# main.net
KiCad netlist of a schematic drawn in Altium Designer
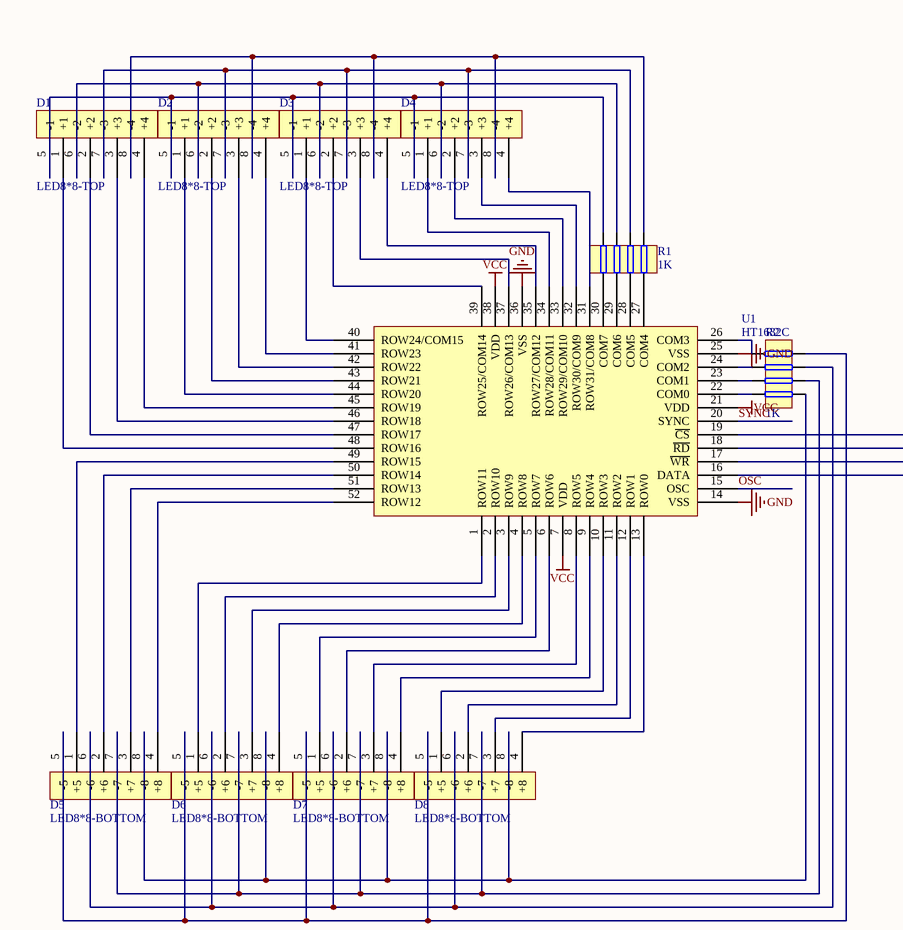
[diagram p0: main.SchDoc, top left]
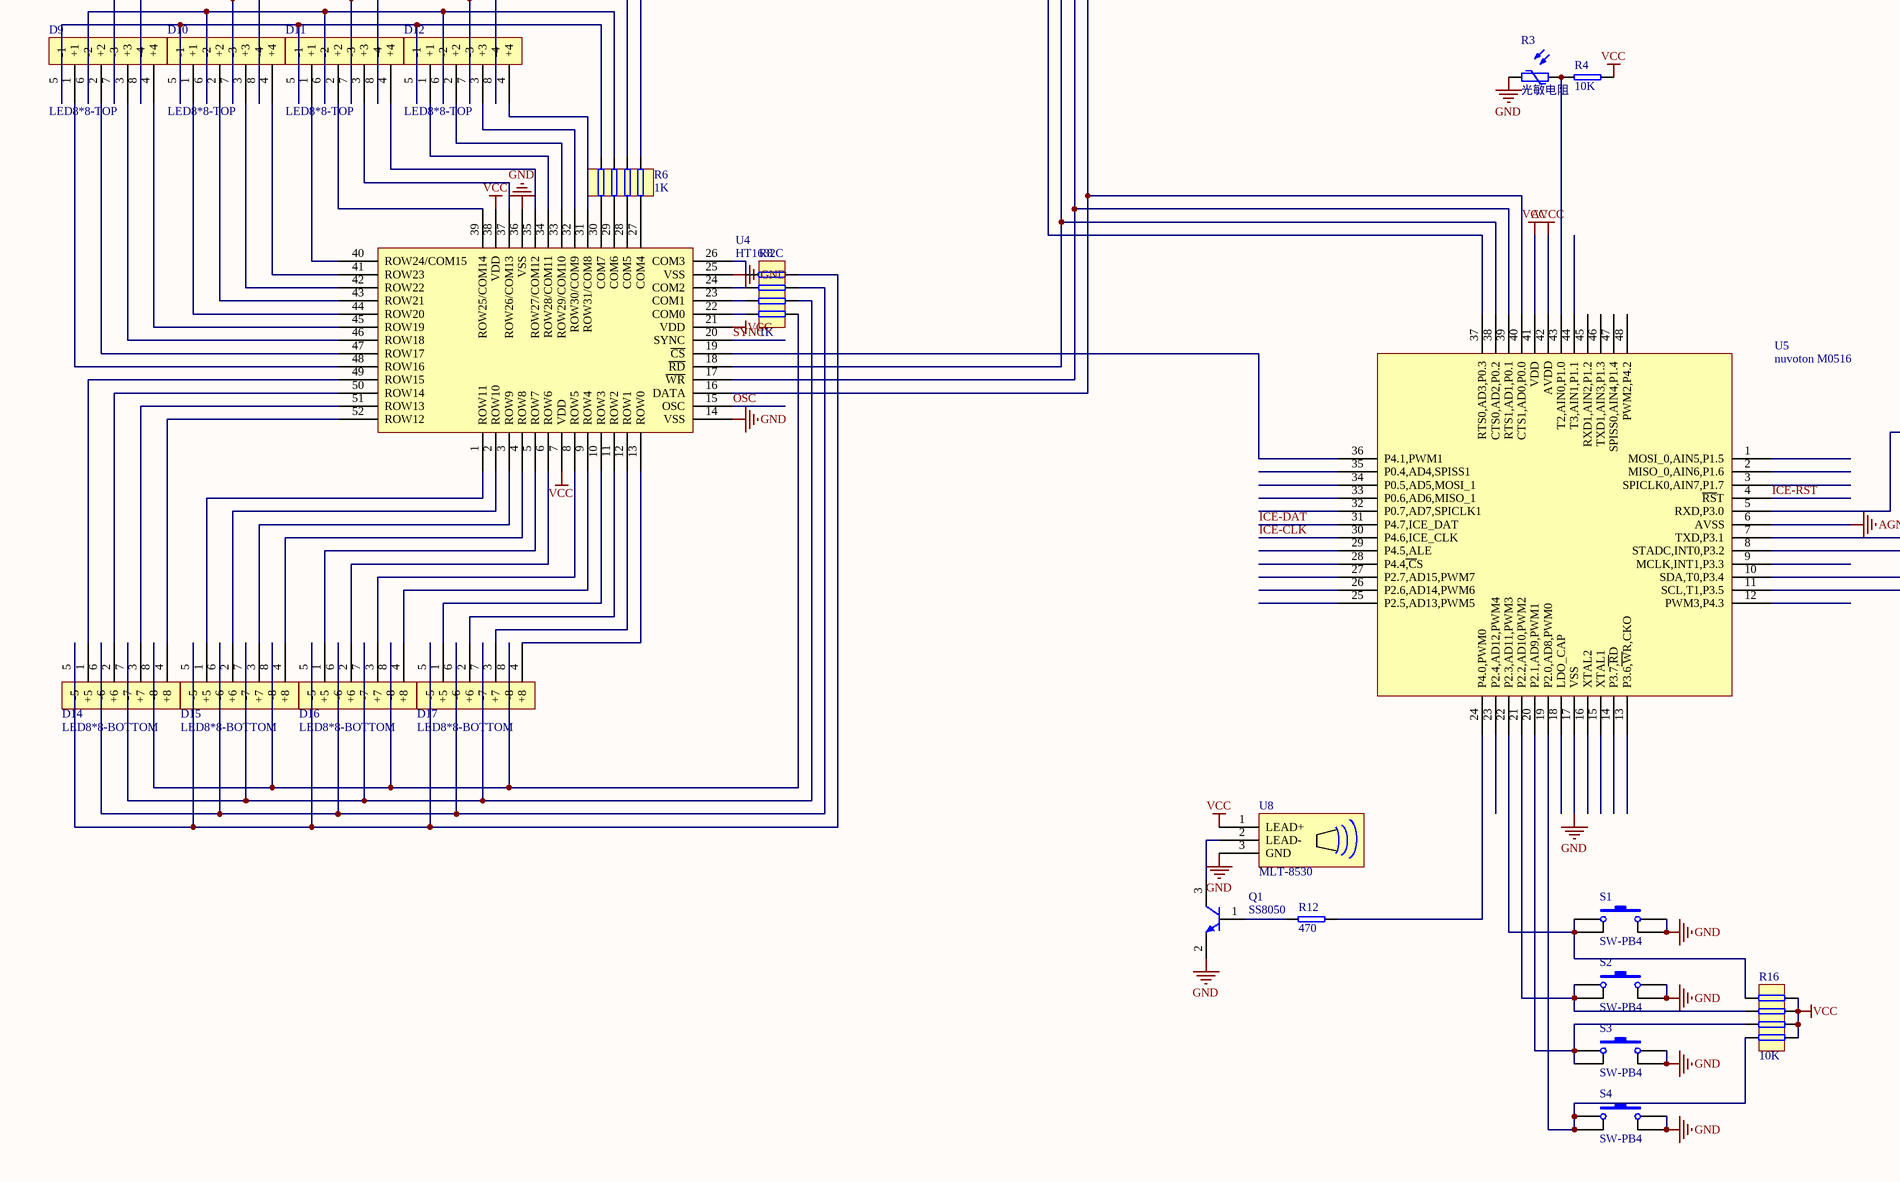
[diagram p1: main.SchDoc, bottom left]
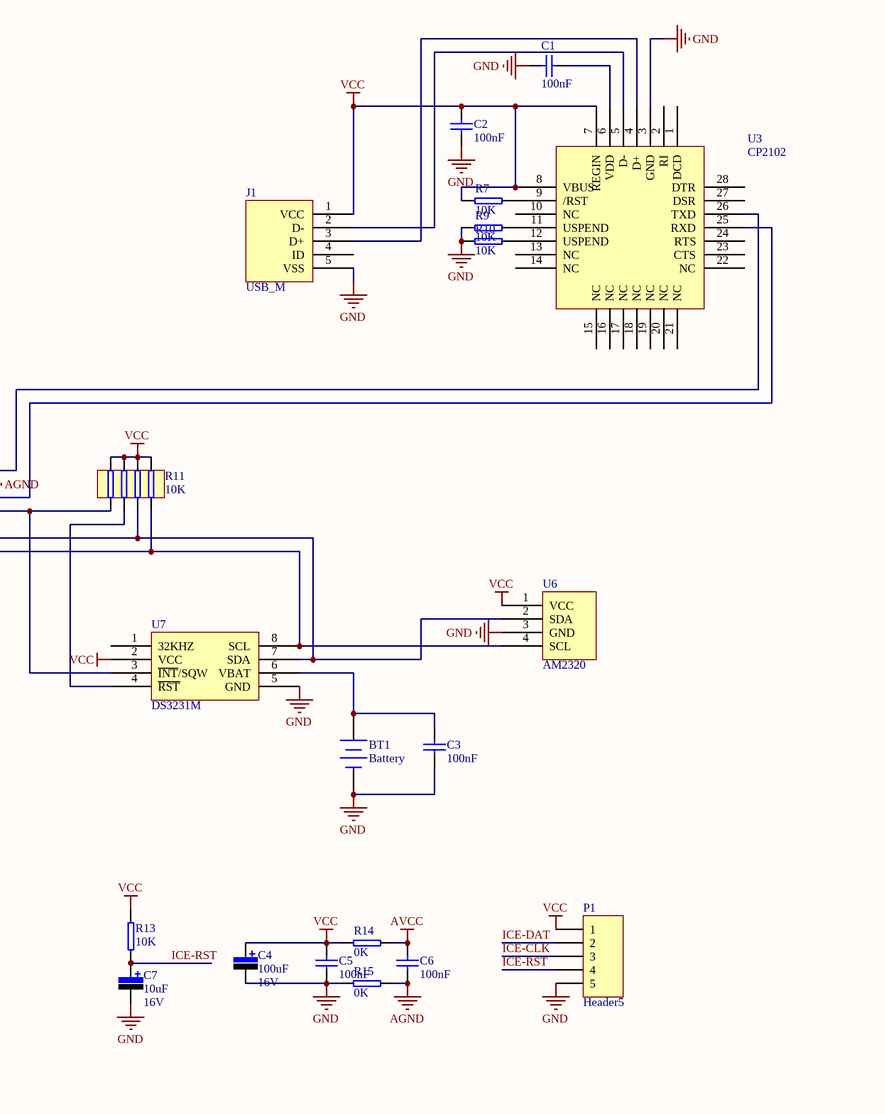
[diagram p2: main.SchDoc, bottom right]

(export (version "E")
  (design (tool "Eeschema 10.0.6"))
  (components
    (comp (ref "BT1")
      (value "Battery")
      (footprint "CR2032-2-1")
      (description "备份电池")
      (fields (field (name "PUBLISHER") "Altium Limited"))
      (libsource (lib "leonLib") (part "Battery"))
    )
    (comp (ref "C1")
      (value "100nF")
      (footprint "C-RAD-0603")
      (description "无极性电容")
      (fields (field (name "Comment") "Cap") (field (name "PUBLISHER") "Altium Limited"))
      (libsource (lib "leonLib") (part "Cap"))
    )
    (comp (ref "C2")
      (value "100nF")
      (footprint "C-RAD-0603")
      (description "无极性电容")
      (fields (field (name "Comment") "Cap") (field (name "PUBLISHER") "Altium Limited"))
      (libsource (lib "leonLib") (part "Cap"))
    )
    (comp (ref "C3")
      (value "100nF")
      (footprint "C-RAD-0603")
      (description "无极性电容")
      (fields (field (name "Comment") "Cap") (field (name "PUBLISHER") "Altium Limited"))
      (libsource (lib "leonLib") (part "Cap"))
    )
    (comp (ref "C4")
      (value "100uF")
      (footprint "CAP-3216")
      (description "极性电解电容")
      (fields
        (field (name "VOL") "16V")
        (field (name "Comment") "Cap Pol")
        (field (name "PUBLISHER") "Altium Limited")
      )
      (libsource (lib "leonLib") (part "Cap Pol"))
    )
    (comp (ref "C5")
      (value "100nF")
      (footprint "C-RAD-0603")
      (description "无极性电容")
      (fields (field (name "Comment") "Cap") (field (name "PUBLISHER") "Altium Limited"))
      (libsource (lib "leonLib") (part "Cap"))
    )
    (comp (ref "C6")
      (value "100nF")
      (footprint "C-RAD-0603")
      (description "无极性电容")
      (fields (field (name "Comment") "Cap") (field (name "PUBLISHER") "Altium Limited"))
      (libsource (lib "leonLib") (part "Cap"))
    )
    (comp (ref "C7")
      (value "10uF")
      (footprint "CAP-3216")
      (description "极性电解电容")
      (fields
        (field (name "VOL") "16V")
        (field (name "Comment") "Cap Pol")
        (field (name "PUBLISHER") "Altium Limited")
      )
      (libsource (lib "leonLib") (part "Cap Pol"))
    )
    (comp (ref "D1")
      (value "LED8*8-TOP")
      (footprint "LED8*8-half")
      (description "8*8LED点阵上半部分")
      (libsource (lib "leonLib") (part "LED8*8-TOP"))
    )
    (comp (ref "D2")
      (value "LED8*8-TOP")
      (footprint "LED8*8-half")
      (description "8*8LED点阵上半部分")
      (libsource (lib "leonLib") (part "LED8*8-TOP"))
    )
    (comp (ref "D3")
      (value "LED8*8-TOP")
      (footprint "LED8*8-half")
      (description "8*8LED点阵上半部分")
      (libsource (lib "leonLib") (part "LED8*8-TOP"))
    )
    (comp (ref "D4")
      (value "LED8*8-TOP")
      (footprint "LED8*8-half")
      (description "8*8LED点阵上半部分")
      (libsource (lib "leonLib") (part "LED8*8-TOP"))
    )
    (comp (ref "D5")
      (value "LED8*8-BOTTOM")
      (footprint "LED8*8-half")
      (description "8*8LED点阵下半部分")
      (libsource (lib "leonLib") (part "LED8*8-BOTTOM"))
    )
    (comp (ref "D6")
      (value "LED8*8-BOTTOM")
      (footprint "LED8*8-half")
      (description "8*8LED点阵下半部分")
      (libsource (lib "leonLib") (part "LED8*8-BOTTOM"))
    )
    (comp (ref "D7")
      (value "LED8*8-BOTTOM")
      (footprint "LED8*8-half")
      (description "8*8LED点阵下半部分")
      (libsource (lib "leonLib") (part "LED8*8-BOTTOM"))
    )
    (comp (ref "D8")
      (value "LED8*8-BOTTOM")
      (footprint "LED8*8-half")
      (description "8*8LED点阵下半部分")
      (libsource (lib "leonLib") (part "LED8*8-BOTTOM"))
    )
    (comp (ref "D9")
      (value "LED8*8-TOP")
      (footprint "LED8*8-half")
      (description "8*8LED点阵上半部分")
      (libsource (lib "leonLib") (part "LED8*8-TOP"))
    )
    (comp (ref "D10")
      (value "LED8*8-TOP")
      (footprint "LED8*8-half")
      (description "8*8LED点阵上半部分")
      (libsource (lib "leonLib") (part "LED8*8-TOP"))
    )
    (comp (ref "D11")
      (value "LED8*8-TOP")
      (footprint "LED8*8-half")
      (description "8*8LED点阵上半部分")
      (libsource (lib "leonLib") (part "LED8*8-TOP"))
    )
    (comp (ref "D12")
      (value "LED8*8-TOP")
      (footprint "LED8*8-half")
      (description "8*8LED点阵上半部分")
      (libsource (lib "leonLib") (part "LED8*8-TOP"))
    )
    (comp (ref "D14")
      (value "LED8*8-BOTTOM")
      (footprint "LED8*8-half")
      (description "8*8LED点阵下半部分")
      (libsource (lib "leonLib") (part "LED8*8-BOTTOM"))
    )
    (comp (ref "D15")
      (value "LED8*8-BOTTOM")
      (footprint "LED8*8-half")
      (description "8*8LED点阵下半部分")
      (libsource (lib "leonLib") (part "LED8*8-BOTTOM"))
    )
    (comp (ref "D16")
      (value "LED8*8-BOTTOM")
      (footprint "LED8*8-half")
      (description "8*8LED点阵下半部分")
      (libsource (lib "leonLib") (part "LED8*8-BOTTOM"))
    )
    (comp (ref "D17")
      (value "LED8*8-BOTTOM")
      (footprint "LED8*8-half")
      (description "8*8LED点阵下半部分")
      (libsource (lib "leonLib") (part "LED8*8-BOTTOM"))
    )
    (comp (ref "J1")
      (value "USB_M")
      (footprint "USB_MICRO")
      (description "MicroUSB接口")
      (libsource (lib "leonLib") (part "USB_M"))
    )
    (comp (ref "P1")
      (value "Header5")
      (footprint "HDR5X1_A")
      (description "接插件")
      (libsource (lib "leonLib") (part "Header5"))
    )
    (comp (ref "Q1")
      (value "SS8050")
      (footprint "SOT-23")
      (description "NPN贴片三极管")
      (fields (field (name "PUBLISHER") "Altium Limited"))
      (libsource (lib "leonLib") (part "SS8050"))
    )
    (comp (ref "R1")
      (value "1K")
      (footprint "RES0603ROW")
      (description "排阻0603*4")
      (libsource (lib "leonLib") (part "Res Row"))
    )
    (comp (ref "R2")
      (value "1K")
      (footprint "RES0603ROW")
      (description "排阻0603*4")
      (libsource (lib "") (part "Res Row_1"))
    )
    (comp (ref "R3") (value "光敏电阻") (footprint "RES3") (libsource (lib "leonLib") (part "res3")))
    (comp (ref "R4")
      (value "10K")
      (footprint "RES_0603")
      (description "贴片电阻")
      (fields (field (name "Comment") "Res1") (field (name "PUBLISHER") "Altium Limited"))
      (libsource (lib "") (part "Res1_1"))
    )
    (comp (ref "R6")
      (value "1K")
      (footprint "RES0603ROW")
      (description "排阻0603*4")
      (libsource (lib "leonLib") (part "Res Row"))
    )
    (comp (ref "R7")
      (value "10K")
      (footprint "RES_0603")
      (description "贴片电阻")
      (fields (field (name "Comment") "Res1") (field (name "PUBLISHER") "Altium Limited"))
      (libsource (lib "") (part "Res1_1"))
    )
    (comp (ref "R8")
      (value "1K")
      (footprint "RES0603ROW")
      (description "排阻0603*4")
      (libsource (lib "") (part "Res Row_1"))
    )
    (comp (ref "R9")
      (value "10K")
      (footprint "RES_0603")
      (description "贴片电阻")
      (fields (field (name "Comment") "Res1") (field (name "PUBLISHER") "Altium Limited"))
      (libsource (lib "") (part "Res1_1"))
    )
    (comp (ref "R10")
      (value "10K")
      (footprint "RES_0603")
      (description "贴片电阻")
      (fields (field (name "Comment") "Res1") (field (name "PUBLISHER") "Altium Limited"))
      (libsource (lib "") (part "Res1_1"))
    )
    (comp (ref "R11")
      (value "10K")
      (footprint "RES0603ROW")
      (description "排阻0603*4")
      (libsource (lib "leonLib") (part "Res Row"))
    )
    (comp (ref "R12")
      (value "470")
      (footprint "RES_0603")
      (description "贴片电阻")
      (fields (field (name "Comment") "Res1") (field (name "PUBLISHER") "Altium Limited"))
      (libsource (lib "") (part "Res1_1"))
    )
    (comp (ref "R13")
      (value "10K")
      (footprint "RES_0603")
      (description "贴片电阻")
      (fields (field (name "Comment") "Res1") (field (name "PUBLISHER") "Altium Limited"))
      (libsource (lib "leonLib") (part "Res1"))
    )
    (comp (ref "R14")
      (value "0K")
      (footprint "RES_0603")
      (description "贴片电阻")
      (fields (field (name "Comment") "Res1") (field (name "PUBLISHER") "Altium Limited"))
      (libsource (lib "") (part "Res1_1"))
    )
    (comp (ref "R15")
      (value "0K")
      (footprint "RES_0603")
      (description "贴片电阻")
      (fields (field (name "Comment") "Res1") (field (name "PUBLISHER") "Altium Limited"))
      (libsource (lib "") (part "Res1_1"))
    )
    (comp (ref "R16")
      (value "10K")
      (footprint "RES0603ROW")
      (description "排阻0603*4")
      (libsource (lib "") (part "Res Row_1"))
    )
    (comp (ref "S1")
      (value "SW-PB4")
      (footprint "SW_PB4_A2_4.5*4.5")
      (description "微动开关")
      (fields (field (name "PUBLISHER") "Altium Limited"))
      (libsource (lib "leonLib") (part "SW-PB4"))
    )
    (comp (ref "S2")
      (value "SW-PB4")
      (footprint "SW_PB4_A2_4.5*4.5")
      (description "微动开关")
      (fields (field (name "PUBLISHER") "Altium Limited"))
      (libsource (lib "leonLib") (part "SW-PB4"))
    )
    (comp (ref "S3")
      (value "SW-PB4")
      (footprint "SW_PB4_A2_4.5*4.5")
      (description "微动开关")
      (fields (field (name "PUBLISHER") "Altium Limited"))
      (libsource (lib "leonLib") (part "SW-PB4"))
    )
    (comp (ref "S4")
      (value "SW-PB4")
      (footprint "SW_PB4_A2_4.5*4.5")
      (description "微动开关")
      (fields (field (name "PUBLISHER") "Altium Limited"))
      (libsource (lib "leonLib") (part "SW-PB4"))
    )
    (comp (ref "U1")
      (value "HT1632C")
      (footprint "QFP52-14mm-1.0mm")
      (description "32×8 & 24×16 LED 驱动芯片")
      (libsource (lib "leonLib") (part "HT1632C"))
    )
    (comp (ref "U3")
      (value "CP2102")
      (footprint "QFN-28")
      (description "USB转TTL芯片")
      (libsource (lib "leonLib") (part "CP2102"))
    )
    (comp (ref "U4")
      (value "HT1632C")
      (footprint "QFP52-14mm-1.0mm")
      (description "32×8 & 24×16 LED 驱动芯片")
      (libsource (lib "leonLib") (part "HT1632C"))
    )
    (comp (ref "U5")
      (value "nuvoton M0516")
      (footprint "LQFP-48_7x7x05P")
      (description "新唐M0516单片机")
      (libsource (lib "leonLib") (part "nuvoton M0516"))
    )
    (comp (ref "U6")
      (value "AM2320")
      (footprint "HDR4X1_A")
      (description "温湿度传感器")
      (libsource (lib "leonLib") (part "AM2320"))
    )
    (comp (ref "U7")
      (value "DS3231M")
      (footprint "SOP-8")
      (description "实时时钟")
      (libsource (lib "leonLib") (part "DS3231M"))
    )
    (comp (ref "U8")
      (value "MLT-8530")
      (footprint "MLT-8530")
      (description "贴片蜂鸣器")
      (libsource (lib "leonLib") (part "MLT-8530"))
    )
  )
  (nets
    (net (code "1") (name "/ICE-CLK") (class "Default")
      (node (ref "P1") (pin "3") (pinfunction "3_3") (pintype "passive"))
      (node (ref "U5") (pin "30") (pinfunction "P4.6,ICE_CLK_30") (pintype "passive"))
    )
    (net (code "2") (name "/ICE-DAT") (class "Default")
      (node (ref "P1") (pin "2") (pinfunction "2_2") (pintype "passive"))
      (node (ref "U5") (pin "31") (pinfunction "P4.7,ICE_DAT_31") (pintype "passive"))
    )
    (net (code "3") (name "/ICE-RST") (class "Default")
      (node (ref "C7") (pin "1") (pinfunction "1_1") (pintype "passive"))
      (node (ref "P1") (pin "4") (pinfunction "4_4") (pintype "passive"))
      (node (ref "R13") (pin "1") (pinfunction "1_1") (pintype "passive"))
      (node (ref "U5") (pin "4") (pinfunction "~{RS}T_4") (pintype "passive"))
    )
    (net (code "4") (name "/OSC") (class "Default")
      (node (ref "U1") (pin "15") (pinfunction "OSC_15") (pintype "passive"))
      (node (ref "U4") (pin "15") (pinfunction "OSC_15") (pintype "passive"))
    )
    (net (code "5") (name "/SYNC") (class "Default")
      (node (ref "U1") (pin "20") (pinfunction "SYNC_20") (pintype "passive"))
      (node (ref "U4") (pin "20") (pinfunction "SYNC_20") (pintype "passive"))
    )
    (net (code "6") (name "AGND") (class "Default")
      (node (ref "C6") (pin "1") (pinfunction "1_1") (pintype "passive"))
      (node (ref "R15") (pin "2") (pinfunction "2_2") (pintype "passive"))
      (node (ref "U5") (pin "6") (pinfunction "AVSS_6") (pintype "passive"))
    )
    (net (code "7") (name "AVCC") (class "Default")
      (node (ref "C6") (pin "2") (pinfunction "2_2") (pintype "passive"))
      (node (ref "R14") (pin "2") (pinfunction "2_2") (pintype "passive"))
      (node (ref "U5") (pin "42") (pinfunction "AVDD_42") (pintype "passive"))
    )
    (net (code "8") (name "GND") (class "Default")
      (node (ref "BT1") (pin "2") (pinfunction "-_2") (pintype "passive"))
      (node (ref "C1") (pin "1") (pinfunction "1_1") (pintype "passive"))
      (node (ref "C2") (pin "1") (pinfunction "1_1") (pintype "passive"))
      (node (ref "C3") (pin "1") (pinfunction "1_1") (pintype "passive"))
      (node (ref "C4") (pin "2") (pinfunction "2_2") (pintype "passive"))
      (node (ref "C5") (pin "1") (pinfunction "1_1") (pintype "passive"))
      (node (ref "C7") (pin "2") (pinfunction "2_2") (pintype "passive"))
      (node (ref "J1") (pin "5") (pinfunction "VSS_5") (pintype "passive"))
      (node (ref "P1") (pin "5") (pinfunction "5_5") (pintype "passive"))
      (node (ref "Q1") (pin "2") (pinfunction "E_2") (pintype "passive"))
      (node (ref "R10") (pin "1") (pinfunction "1_1") (pintype "passive"))
      (node (ref "R15") (pin "1") (pinfunction "1_1") (pintype "passive"))
      (node (ref "R3") (pin "1") (pinfunction "1_1") (pintype "passive"))
      (node (ref "R9") (pin "1") (pinfunction "1_1") (pintype "passive"))
      (node (ref "S1") (pin "2") (pinfunction "2_2") (pintype "passive"))
      (node (ref "S1") (pin "3") (pinfunction "3_3") (pintype "passive"))
      (node (ref "S2") (pin "2") (pinfunction "2_2") (pintype "passive"))
      (node (ref "S2") (pin "3") (pinfunction "3_3") (pintype "passive"))
      (node (ref "S3") (pin "2") (pinfunction "2_2") (pintype "passive"))
      (node (ref "S3") (pin "3") (pinfunction "3_3") (pintype "passive"))
      (node (ref "S4") (pin "2") (pinfunction "2_2") (pintype "passive"))
      (node (ref "S4") (pin "3") (pinfunction "3_3") (pintype "passive"))
      (node (ref "U1") (pin "14") (pinfunction "VSS_14") (pintype "passive"))
      (node (ref "U1") (pin "25") (pinfunction "VSS_25") (pintype "passive"))
      (node (ref "U1") (pin "36") (pinfunction "VSS_36") (pintype "passive"))
      (node (ref "U3") (pin "3") (pinfunction "GND_3") (pintype "passive"))
      (node (ref "U4") (pin "14") (pinfunction "VSS_14") (pintype "passive"))
      (node (ref "U4") (pin "25") (pinfunction "VSS_25") (pintype "passive"))
      (node (ref "U4") (pin "36") (pinfunction "VSS_36") (pintype "passive"))
      (node (ref "U5") (pin "17") (pinfunction "VSS_17") (pintype "passive"))
      (node (ref "U6") (pin "3") (pinfunction "GND_3") (pintype "passive"))
      (node (ref "U7") (pin "5") (pinfunction "GND_5") (pintype "passive"))
      (node (ref "U8") (pin "3") (pinfunction "GND_3") (pintype "passive"))
    )
    (net (code "9") (name "Net-(BT1-+)") (class "Default")
      (node (ref "BT1") (pin "1") (pinfunction "+_1") (pintype "passive"))
      (node (ref "C3") (pin "2") (pinfunction "2_2") (pintype "passive"))
      (node (ref "U7") (pin "6") (pinfunction "VBAT_6") (pintype "passive"))
    )
    (net (code "10") (name "Net-(D1-+1)") (class "Default")
      (node (ref "D1") (pin "1") (pinfunction "+1_1") (pintype "passive"))
      (node (ref "U1") (pin "48") (pinfunction "ROW16_48") (pintype "passive"))
    )
    (net (code "11") (name "Net-(D1-+2)") (class "Default")
      (node (ref "D1") (pin "2") (pinfunction "+2_2") (pintype "passive"))
      (node (ref "U1") (pin "47") (pinfunction "ROW17_47") (pintype "passive"))
    )
    (net (code "12") (name "Net-(D1-+3)") (class "Default")
      (node (ref "D1") (pin "3") (pinfunction "+3_3") (pintype "passive"))
      (node (ref "U1") (pin "46") (pinfunction "ROW18_46") (pintype "passive"))
    )
    (net (code "13") (name "Net-(D1-+4)") (class "Default")
      (node (ref "D1") (pin "4") (pinfunction "+4_4") (pintype "passive"))
      (node (ref "U1") (pin "45") (pinfunction "ROW19_45") (pintype "passive"))
    )
    (net (code "14") (name "Net-(D1--1)") (class "Default")
      (node (ref "D1") (pin "5") (pinfunction "-1_5") (pintype "passive"))
      (node (ref "D2") (pin "5") (pinfunction "-1_5") (pintype "passive"))
      (node (ref "D3") (pin "5") (pinfunction "-1_5") (pintype "passive"))
      (node (ref "D4") (pin "5") (pinfunction "-1_5") (pintype "passive"))
      (node (ref "R1") (pin "8") (pinfunction "8_8") (pintype "passive"))
    )
    (net (code "15") (name "Net-(D1--2)") (class "Default")
      (node (ref "D1") (pin "6") (pinfunction "-2_6") (pintype "passive"))
      (node (ref "D2") (pin "6") (pinfunction "-2_6") (pintype "passive"))
      (node (ref "D3") (pin "6") (pinfunction "-2_6") (pintype "passive"))
      (node (ref "D4") (pin "6") (pinfunction "-2_6") (pintype "passive"))
      (node (ref "R1") (pin "7") (pinfunction "7_7") (pintype "passive"))
    )
    (net (code "16") (name "Net-(D1--3)") (class "Default")
      (node (ref "D1") (pin "7") (pinfunction "-3_7") (pintype "passive"))
      (node (ref "D2") (pin "7") (pinfunction "-3_7") (pintype "passive"))
      (node (ref "D3") (pin "7") (pinfunction "-3_7") (pintype "passive"))
      (node (ref "D4") (pin "7") (pinfunction "-3_7") (pintype "passive"))
      (node (ref "R1") (pin "6") (pinfunction "6_6") (pintype "passive"))
    )
    (net (code "17") (name "Net-(D1--4)") (class "Default")
      (node (ref "D1") (pin "8") (pinfunction "-4_8") (pintype "passive"))
      (node (ref "D2") (pin "8") (pinfunction "-4_8") (pintype "passive"))
      (node (ref "D3") (pin "8") (pinfunction "-4_8") (pintype "passive"))
      (node (ref "D4") (pin "8") (pinfunction "-4_8") (pintype "passive"))
      (node (ref "R1") (pin "5") (pinfunction "5_5") (pintype "passive"))
    )
    (net (code "18") (name "Net-(D2-+1)") (class "Default")
      (node (ref "D2") (pin "1") (pinfunction "+1_1") (pintype "passive"))
      (node (ref "U1") (pin "44") (pinfunction "ROW20_44") (pintype "passive"))
    )
    (net (code "19") (name "Net-(D2-+2)") (class "Default")
      (node (ref "D2") (pin "2") (pinfunction "+2_2") (pintype "passive"))
      (node (ref "U1") (pin "43") (pinfunction "ROW21_43") (pintype "passive"))
    )
    (net (code "20") (name "Net-(D2-+3)") (class "Default")
      (node (ref "D2") (pin "3") (pinfunction "+3_3") (pintype "passive"))
      (node (ref "U1") (pin "42") (pinfunction "ROW22_42") (pintype "passive"))
    )
    (net (code "21") (name "Net-(D2-+4)") (class "Default")
      (node (ref "D2") (pin "4") (pinfunction "+4_4") (pintype "passive"))
      (node (ref "U1") (pin "41") (pinfunction "ROW23_41") (pintype "passive"))
    )
    (net (code "22") (name "Net-(D3-+1)") (class "Default")
      (node (ref "D3") (pin "1") (pinfunction "+1_1") (pintype "passive"))
      (node (ref "U1") (pin "40") (pinfunction "ROW24/COM15_40") (pintype "passive"))
    )
    (net (code "23") (name "Net-(D3-+2)") (class "Default")
      (node (ref "D3") (pin "2") (pinfunction "+2_2") (pintype "passive"))
      (node (ref "U1") (pin "39") (pinfunction "ROW25/COM14_39") (pintype "passive"))
    )
    (net (code "24") (name "Net-(D3-+3)") (class "Default")
      (node (ref "D3") (pin "3") (pinfunction "+3_3") (pintype "passive"))
      (node (ref "U1") (pin "37") (pinfunction "ROW26/COM13_37") (pintype "passive"))
    )
    (net (code "25") (name "Net-(D3-+4)") (class "Default")
      (node (ref "D3") (pin "4") (pinfunction "+4_4") (pintype "passive"))
      (node (ref "U1") (pin "35") (pinfunction "ROW27/COM12_35") (pintype "passive"))
    )
    (net (code "26") (name "Net-(D4-+1)") (class "Default")
      (node (ref "D4") (pin "1") (pinfunction "+1_1") (pintype "passive"))
      (node (ref "U1") (pin "34") (pinfunction "ROW28/COM11_34") (pintype "passive"))
    )
    (net (code "27") (name "Net-(D4-+2)") (class "Default")
      (node (ref "D4") (pin "2") (pinfunction "+2_2") (pintype "passive"))
      (node (ref "U1") (pin "33") (pinfunction "ROW29/COM10_33") (pintype "passive"))
    )
    (net (code "28") (name "Net-(D4-+3)") (class "Default")
      (node (ref "D4") (pin "3") (pinfunction "+3_3") (pintype "passive"))
      (node (ref "U1") (pin "32") (pinfunction "ROW30/COM9_32") (pintype "passive"))
    )
    (net (code "29") (name "Net-(D4-+4)") (class "Default")
      (node (ref "D4") (pin "4") (pinfunction "+4_4") (pintype "passive"))
      (node (ref "U1") (pin "31") (pinfunction "ROW31/COM8_31") (pintype "passive"))
    )
    (net (code "30") (name "Net-(D5-+5)") (class "Default")
      (node (ref "D5") (pin "1") (pinfunction "+5_1") (pintype "passive"))
      (node (ref "U1") (pin "49") (pinfunction "ROW15_49") (pintype "passive"))
    )
    (net (code "31") (name "Net-(D5-+6)") (class "Default")
      (node (ref "D5") (pin "2") (pinfunction "+6_2") (pintype "passive"))
      (node (ref "U1") (pin "50") (pinfunction "ROW14_50") (pintype "passive"))
    )
    (net (code "32") (name "Net-(D5-+7)") (class "Default")
      (node (ref "D5") (pin "3") (pinfunction "+7_3") (pintype "passive"))
      (node (ref "U1") (pin "51") (pinfunction "ROW13_51") (pintype "passive"))
    )
    (net (code "33") (name "Net-(D5-+8)") (class "Default")
      (node (ref "D5") (pin "4") (pinfunction "+8_4") (pintype "passive"))
      (node (ref "U1") (pin "52") (pinfunction "ROW12_52") (pintype "passive"))
    )
    (net (code "34") (name "Net-(D5--5)") (class "Default")
      (node (ref "D5") (pin "5") (pinfunction "-5_5") (pintype "passive"))
      (node (ref "D6") (pin "5") (pinfunction "-5_5") (pintype "passive"))
      (node (ref "D7") (pin "5") (pinfunction "-5_5") (pintype "passive"))
      (node (ref "D8") (pin "5") (pinfunction "-5_5") (pintype "passive"))
      (node (ref "R2") (pin "8") (pinfunction "8_8") (pintype "passive"))
    )
    (net (code "35") (name "Net-(D5--6)") (class "Default")
      (node (ref "D5") (pin "6") (pinfunction "-6_6") (pintype "passive"))
      (node (ref "D6") (pin "6") (pinfunction "-6_6") (pintype "passive"))
      (node (ref "D7") (pin "6") (pinfunction "-6_6") (pintype "passive"))
      (node (ref "D8") (pin "6") (pinfunction "-6_6") (pintype "passive"))
      (node (ref "R2") (pin "7") (pinfunction "7_7") (pintype "passive"))
    )
    (net (code "36") (name "Net-(D5--7)") (class "Default")
      (node (ref "D5") (pin "7") (pinfunction "-7_7") (pintype "passive"))
      (node (ref "D6") (pin "7") (pinfunction "-7_7") (pintype "passive"))
      (node (ref "D7") (pin "7") (pinfunction "-7_7") (pintype "passive"))
      (node (ref "D8") (pin "7") (pinfunction "-7_7") (pintype "passive"))
      (node (ref "R2") (pin "6") (pinfunction "6_6") (pintype "passive"))
    )
    (net (code "37") (name "Net-(D5--8)") (class "Default")
      (node (ref "D5") (pin "8") (pinfunction "-8_8") (pintype "passive"))
      (node (ref "D6") (pin "8") (pinfunction "-8_8") (pintype "passive"))
      (node (ref "D7") (pin "8") (pinfunction "-8_8") (pintype "passive"))
      (node (ref "D8") (pin "8") (pinfunction "-8_8") (pintype "passive"))
      (node (ref "R2") (pin "5") (pinfunction "5_5") (pintype "passive"))
    )
    (net (code "38") (name "Net-(D6-+5)") (class "Default")
      (node (ref "D6") (pin "1") (pinfunction "+5_1") (pintype "passive"))
      (node (ref "U1") (pin "1") (pinfunction "ROW11_1") (pintype "passive"))
    )
    (net (code "39") (name "Net-(D6-+6)") (class "Default")
      (node (ref "D6") (pin "2") (pinfunction "+6_2") (pintype "passive"))
      (node (ref "U1") (pin "2") (pinfunction "ROW10_2") (pintype "passive"))
    )
    (net (code "40") (name "Net-(D6-+7)") (class "Default")
      (node (ref "D6") (pin "3") (pinfunction "+7_3") (pintype "passive"))
      (node (ref "U1") (pin "3") (pinfunction "ROW9_3") (pintype "passive"))
    )
    (net (code "41") (name "Net-(D6-+8)") (class "Default")
      (node (ref "D6") (pin "4") (pinfunction "+8_4") (pintype "passive"))
      (node (ref "U1") (pin "4") (pinfunction "ROW8_4") (pintype "passive"))
    )
    (net (code "42") (name "Net-(D7-+5)") (class "Default")
      (node (ref "D7") (pin "1") (pinfunction "+5_1") (pintype "passive"))
      (node (ref "U1") (pin "5") (pinfunction "ROW7_5") (pintype "passive"))
    )
    (net (code "43") (name "Net-(D7-+6)") (class "Default")
      (node (ref "D7") (pin "2") (pinfunction "+6_2") (pintype "passive"))
      (node (ref "U1") (pin "6") (pinfunction "ROW6_6") (pintype "passive"))
    )
    (net (code "44") (name "Net-(D7-+7)") (class "Default")
      (node (ref "D7") (pin "3") (pinfunction "+7_3") (pintype "passive"))
      (node (ref "U1") (pin "8") (pinfunction "ROW5_8") (pintype "passive"))
    )
    (net (code "45") (name "Net-(D7-+8)") (class "Default")
      (node (ref "D7") (pin "4") (pinfunction "+8_4") (pintype "passive"))
      (node (ref "U1") (pin "9") (pinfunction "ROW4_9") (pintype "passive"))
    )
    (net (code "46") (name "Net-(D8-+5)") (class "Default")
      (node (ref "D8") (pin "1") (pinfunction "+5_1") (pintype "passive"))
      (node (ref "U1") (pin "10") (pinfunction "ROW3_10") (pintype "passive"))
    )
    (net (code "47") (name "Net-(D8-+6)") (class "Default")
      (node (ref "D8") (pin "2") (pinfunction "+6_2") (pintype "passive"))
      (node (ref "U1") (pin "11") (pinfunction "ROW2_11") (pintype "passive"))
    )
    (net (code "48") (name "Net-(D8-+7)") (class "Default")
      (node (ref "D8") (pin "3") (pinfunction "+7_3") (pintype "passive"))
      (node (ref "U1") (pin "12") (pinfunction "ROW1_12") (pintype "passive"))
    )
    (net (code "49") (name "Net-(D8-+8)") (class "Default")
      (node (ref "D8") (pin "4") (pinfunction "+8_4") (pintype "passive"))
      (node (ref "U1") (pin "13") (pinfunction "ROW0_13") (pintype "passive"))
    )
    (net (code "50") (name "Net-(D9-+1)") (class "Default")
      (node (ref "D9") (pin "1") (pinfunction "+1_1") (pintype "passive"))
      (node (ref "U4") (pin "48") (pinfunction "ROW16_48") (pintype "passive"))
    )
    (net (code "51") (name "Net-(D9-+2)") (class "Default")
      (node (ref "D9") (pin "2") (pinfunction "+2_2") (pintype "passive"))
      (node (ref "U4") (pin "47") (pinfunction "ROW17_47") (pintype "passive"))
    )
    (net (code "52") (name "Net-(D9-+3)") (class "Default")
      (node (ref "D9") (pin "3") (pinfunction "+3_3") (pintype "passive"))
      (node (ref "U4") (pin "46") (pinfunction "ROW18_46") (pintype "passive"))
    )
    (net (code "53") (name "Net-(D9-+4)") (class "Default")
      (node (ref "D9") (pin "4") (pinfunction "+4_4") (pintype "passive"))
      (node (ref "U4") (pin "45") (pinfunction "ROW19_45") (pintype "passive"))
    )
    (net (code "54") (name "Net-(D10-+1)") (class "Default")
      (node (ref "D10") (pin "1") (pinfunction "+1_1") (pintype "passive"))
      (node (ref "U4") (pin "44") (pinfunction "ROW20_44") (pintype "passive"))
    )
    (net (code "55") (name "Net-(D10-+2)") (class "Default")
      (node (ref "D10") (pin "2") (pinfunction "+2_2") (pintype "passive"))
      (node (ref "U4") (pin "43") (pinfunction "ROW21_43") (pintype "passive"))
    )
    (net (code "56") (name "Net-(D10-+3)") (class "Default")
      (node (ref "D10") (pin "3") (pinfunction "+3_3") (pintype "passive"))
      (node (ref "U4") (pin "42") (pinfunction "ROW22_42") (pintype "passive"))
    )
    (net (code "57") (name "Net-(D10-+4)") (class "Default")
      (node (ref "D10") (pin "4") (pinfunction "+4_4") (pintype "passive"))
      (node (ref "U4") (pin "41") (pinfunction "ROW23_41") (pintype "passive"))
    )
    (net (code "58") (name "Net-(D10--1)") (class "Default")
      (node (ref "D10") (pin "5") (pinfunction "-1_5") (pintype "passive"))
      (node (ref "D11") (pin "5") (pinfunction "-1_5") (pintype "passive"))
      (node (ref "D12") (pin "5") (pinfunction "-1_5") (pintype "passive"))
      (node (ref "D9") (pin "5") (pinfunction "-1_5") (pintype "passive"))
      (node (ref "R6") (pin "8") (pinfunction "8_8") (pintype "passive"))
    )
    (net (code "59") (name "Net-(D10--2)") (class "Default")
      (node (ref "D10") (pin "6") (pinfunction "-2_6") (pintype "passive"))
      (node (ref "D11") (pin "6") (pinfunction "-2_6") (pintype "passive"))
      (node (ref "D12") (pin "6") (pinfunction "-2_6") (pintype "passive"))
      (node (ref "D9") (pin "6") (pinfunction "-2_6") (pintype "passive"))
      (node (ref "R6") (pin "7") (pinfunction "7_7") (pintype "passive"))
    )
    (net (code "60") (name "Net-(D10--3)") (class "Default")
      (node (ref "D10") (pin "7") (pinfunction "-3_7") (pintype "passive"))
      (node (ref "D11") (pin "7") (pinfunction "-3_7") (pintype "passive"))
      (node (ref "D12") (pin "7") (pinfunction "-3_7") (pintype "passive"))
      (node (ref "D9") (pin "7") (pinfunction "-3_7") (pintype "passive"))
      (node (ref "R6") (pin "6") (pinfunction "6_6") (pintype "passive"))
    )
    (net (code "61") (name "Net-(D10--4)") (class "Default")
      (node (ref "D10") (pin "8") (pinfunction "-4_8") (pintype "passive"))
      (node (ref "D11") (pin "8") (pinfunction "-4_8") (pintype "passive"))
      (node (ref "D12") (pin "8") (pinfunction "-4_8") (pintype "passive"))
      (node (ref "D9") (pin "8") (pinfunction "-4_8") (pintype "passive"))
      (node (ref "R6") (pin "5") (pinfunction "5_5") (pintype "passive"))
    )
    (net (code "62") (name "Net-(D11-+1)") (class "Default")
      (node (ref "D11") (pin "1") (pinfunction "+1_1") (pintype "passive"))
      (node (ref "U4") (pin "40") (pinfunction "ROW24/COM15_40") (pintype "passive"))
    )
    (net (code "63") (name "Net-(D11-+2)") (class "Default")
      (node (ref "D11") (pin "2") (pinfunction "+2_2") (pintype "passive"))
      (node (ref "U4") (pin "39") (pinfunction "ROW25/COM14_39") (pintype "passive"))
    )
    (net (code "64") (name "Net-(D11-+3)") (class "Default")
      (node (ref "D11") (pin "3") (pinfunction "+3_3") (pintype "passive"))
      (node (ref "U4") (pin "37") (pinfunction "ROW26/COM13_37") (pintype "passive"))
    )
    (net (code "65") (name "Net-(D11-+4)") (class "Default")
      (node (ref "D11") (pin "4") (pinfunction "+4_4") (pintype "passive"))
      (node (ref "U4") (pin "35") (pinfunction "ROW27/COM12_35") (pintype "passive"))
    )
    (net (code "66") (name "Net-(D12-+1)") (class "Default")
      (node (ref "D12") (pin "1") (pinfunction "+1_1") (pintype "passive"))
      (node (ref "U4") (pin "34") (pinfunction "ROW28/COM11_34") (pintype "passive"))
    )
    (net (code "67") (name "Net-(D12-+2)") (class "Default")
      (node (ref "D12") (pin "2") (pinfunction "+2_2") (pintype "passive"))
      (node (ref "U4") (pin "33") (pinfunction "ROW29/COM10_33") (pintype "passive"))
    )
    (net (code "68") (name "Net-(D12-+3)") (class "Default")
      (node (ref "D12") (pin "3") (pinfunction "+3_3") (pintype "passive"))
      (node (ref "U4") (pin "32") (pinfunction "ROW30/COM9_32") (pintype "passive"))
    )
    (net (code "69") (name "Net-(D12-+4)") (class "Default")
      (node (ref "D12") (pin "4") (pinfunction "+4_4") (pintype "passive"))
      (node (ref "U4") (pin "31") (pinfunction "ROW31/COM8_31") (pintype "passive"))
    )
    (net (code "70") (name "Net-(D14-+5)") (class "Default")
      (node (ref "D14") (pin "1") (pinfunction "+5_1") (pintype "passive"))
      (node (ref "U4") (pin "49") (pinfunction "ROW15_49") (pintype "passive"))
    )
    (net (code "71") (name "Net-(D14-+6)") (class "Default")
      (node (ref "D14") (pin "2") (pinfunction "+6_2") (pintype "passive"))
      (node (ref "U4") (pin "50") (pinfunction "ROW14_50") (pintype "passive"))
    )
    (net (code "72") (name "Net-(D14-+7)") (class "Default")
      (node (ref "D14") (pin "3") (pinfunction "+7_3") (pintype "passive"))
      (node (ref "U4") (pin "51") (pinfunction "ROW13_51") (pintype "passive"))
    )
    (net (code "73") (name "Net-(D14-+8)") (class "Default")
      (node (ref "D14") (pin "4") (pinfunction "+8_4") (pintype "passive"))
      (node (ref "U4") (pin "52") (pinfunction "ROW12_52") (pintype "passive"))
    )
    (net (code "74") (name "Net-(D14--5)") (class "Default")
      (node (ref "D14") (pin "5") (pinfunction "-5_5") (pintype "passive"))
      (node (ref "D15") (pin "5") (pinfunction "-5_5") (pintype "passive"))
      (node (ref "D16") (pin "5") (pinfunction "-5_5") (pintype "passive"))
      (node (ref "D17") (pin "5") (pinfunction "-5_5") (pintype "passive"))
      (node (ref "R8") (pin "8") (pinfunction "8_8") (pintype "passive"))
    )
    (net (code "75") (name "Net-(D14--6)") (class "Default")
      (node (ref "D14") (pin "6") (pinfunction "-6_6") (pintype "passive"))
      (node (ref "D15") (pin "6") (pinfunction "-6_6") (pintype "passive"))
      (node (ref "D16") (pin "6") (pinfunction "-6_6") (pintype "passive"))
      (node (ref "D17") (pin "6") (pinfunction "-6_6") (pintype "passive"))
      (node (ref "R8") (pin "7") (pinfunction "7_7") (pintype "passive"))
    )
    (net (code "76") (name "Net-(D14--7)") (class "Default")
      (node (ref "D14") (pin "7") (pinfunction "-7_7") (pintype "passive"))
      (node (ref "D15") (pin "7") (pinfunction "-7_7") (pintype "passive"))
      (node (ref "D16") (pin "7") (pinfunction "-7_7") (pintype "passive"))
      (node (ref "D17") (pin "7") (pinfunction "-7_7") (pintype "passive"))
      (node (ref "R8") (pin "6") (pinfunction "6_6") (pintype "passive"))
    )
    (net (code "77") (name "Net-(D14--8)") (class "Default")
      (node (ref "D14") (pin "8") (pinfunction "-8_8") (pintype "passive"))
      (node (ref "D15") (pin "8") (pinfunction "-8_8") (pintype "passive"))
      (node (ref "D16") (pin "8") (pinfunction "-8_8") (pintype "passive"))
      (node (ref "D17") (pin "8") (pinfunction "-8_8") (pintype "passive"))
      (node (ref "R8") (pin "5") (pinfunction "5_5") (pintype "passive"))
    )
    (net (code "78") (name "Net-(D15-+5)") (class "Default")
      (node (ref "D15") (pin "1") (pinfunction "+5_1") (pintype "passive"))
      (node (ref "U4") (pin "1") (pinfunction "ROW11_1") (pintype "passive"))
    )
    (net (code "79") (name "Net-(D15-+6)") (class "Default")
      (node (ref "D15") (pin "2") (pinfunction "+6_2") (pintype "passive"))
      (node (ref "U4") (pin "2") (pinfunction "ROW10_2") (pintype "passive"))
    )
    (net (code "80") (name "Net-(D15-+7)") (class "Default")
      (node (ref "D15") (pin "3") (pinfunction "+7_3") (pintype "passive"))
      (node (ref "U4") (pin "3") (pinfunction "ROW9_3") (pintype "passive"))
    )
    (net (code "81") (name "Net-(D15-+8)") (class "Default")
      (node (ref "D15") (pin "4") (pinfunction "+8_4") (pintype "passive"))
      (node (ref "U4") (pin "4") (pinfunction "ROW8_4") (pintype "passive"))
    )
    (net (code "82") (name "Net-(D16-+5)") (class "Default")
      (node (ref "D16") (pin "1") (pinfunction "+5_1") (pintype "passive"))
      (node (ref "U4") (pin "5") (pinfunction "ROW7_5") (pintype "passive"))
    )
    (net (code "83") (name "Net-(D16-+6)") (class "Default")
      (node (ref "D16") (pin "2") (pinfunction "+6_2") (pintype "passive"))
      (node (ref "U4") (pin "6") (pinfunction "ROW6_6") (pintype "passive"))
    )
    (net (code "84") (name "Net-(D16-+7)") (class "Default")
      (node (ref "D16") (pin "3") (pinfunction "+7_3") (pintype "passive"))
      (node (ref "U4") (pin "8") (pinfunction "ROW5_8") (pintype "passive"))
    )
    (net (code "85") (name "Net-(D16-+8)") (class "Default")
      (node (ref "D16") (pin "4") (pinfunction "+8_4") (pintype "passive"))
      (node (ref "U4") (pin "9") (pinfunction "ROW4_9") (pintype "passive"))
    )
    (net (code "86") (name "Net-(D17-+5)") (class "Default")
      (node (ref "D17") (pin "1") (pinfunction "+5_1") (pintype "passive"))
      (node (ref "U4") (pin "10") (pinfunction "ROW3_10") (pintype "passive"))
    )
    (net (code "87") (name "Net-(D17-+6)") (class "Default")
      (node (ref "D17") (pin "2") (pinfunction "+6_2") (pintype "passive"))
      (node (ref "U4") (pin "11") (pinfunction "ROW2_11") (pintype "passive"))
    )
    (net (code "88") (name "Net-(D17-+7)") (class "Default")
      (node (ref "D17") (pin "3") (pinfunction "+7_3") (pintype "passive"))
      (node (ref "U4") (pin "12") (pinfunction "ROW1_12") (pintype "passive"))
    )
    (net (code "89") (name "Net-(D17-+8)") (class "Default")
      (node (ref "D17") (pin "4") (pinfunction "+8_4") (pintype "passive"))
      (node (ref "U4") (pin "13") (pinfunction "ROW0_13") (pintype "passive"))
    )
    (net (code "90") (name "Net-(J1-D+)") (class "Default")
      (node (ref "J1") (pin "3") (pinfunction "D+_3") (pintype "passive"))
      (node (ref "U3") (pin "4") (pinfunction "D+_4") (pintype "passive"))
    )
    (net (code "91") (name "Net-(J1-D-)") (class "Default")
      (node (ref "J1") (pin "2") (pinfunction "D-_2") (pintype "passive"))
      (node (ref "U3") (pin "5") (pinfunction "D-_5") (pintype "passive"))
    )
    (net (code "92") (name "Net-(Q1-B)") (class "Default")
      (node (ref "Q1") (pin "1") (pinfunction "B_1") (pintype "passive"))
      (node (ref "R12") (pin "1") (pinfunction "1_1") (pintype "passive"))
    )
    (net (code "93") (name "Net-(Q1-C)") (class "Default")
      (node (ref "Q1") (pin "3") (pinfunction "C_3") (pintype "passive"))
      (node (ref "U8") (pin "2") (pinfunction "LEAD-_2") (pintype "passive"))
    )
    (net (code "94") (name "Net-(R9-Pad2)") (class "Default")
      (node (ref "R9") (pin "2") (pinfunction "2_2") (pintype "passive"))
      (node (ref "U3") (pin "11") (pinfunction "USPEND_11") (pintype "passive"))
    )
    (net (code "95") (name "Net-(R10-Pad2)") (class "Default")
      (node (ref "R10") (pin "2") (pinfunction "2_2") (pintype "passive"))
      (node (ref "U3") (pin "12") (pinfunction "USPEND_12") (pintype "passive"))
    )
    (net (code "96") (name "Net-(U1-COM0)") (class "Default")
      (node (ref "R2") (pin "4") (pinfunction "4_4") (pintype "passive"))
      (node (ref "U1") (pin "22") (pinfunction "COM0_22") (pintype "passive"))
    )
    (net (code "97") (name "Net-(U1-COM1)") (class "Default")
      (node (ref "R2") (pin "3") (pinfunction "3_3") (pintype "passive"))
      (node (ref "U1") (pin "23") (pinfunction "COM1_23") (pintype "passive"))
    )
    (net (code "98") (name "Net-(U1-COM2)") (class "Default")
      (node (ref "R2") (pin "2") (pinfunction "2_2") (pintype "passive"))
      (node (ref "U1") (pin "24") (pinfunction "COM2_24") (pintype "passive"))
    )
    (net (code "99") (name "Net-(U1-COM3)") (class "Default")
      (node (ref "R2") (pin "1") (pinfunction "1_1") (pintype "passive"))
      (node (ref "U1") (pin "26") (pinfunction "COM3_26") (pintype "passive"))
    )
    (net (code "100") (name "Net-(U1-COM4)") (class "Default")
      (node (ref "R1") (pin "4") (pinfunction "4_4") (pintype "passive"))
      (node (ref "U1") (pin "27") (pinfunction "COM4_27") (pintype "passive"))
    )
    (net (code "101") (name "Net-(U1-COM5)") (class "Default")
      (node (ref "R1") (pin "3") (pinfunction "3_3") (pintype "passive"))
      (node (ref "U1") (pin "28") (pinfunction "COM5_28") (pintype "passive"))
    )
    (net (code "102") (name "Net-(U1-COM6)") (class "Default")
      (node (ref "R1") (pin "2") (pinfunction "2_2") (pintype "passive"))
      (node (ref "U1") (pin "29") (pinfunction "COM6_29") (pintype "passive"))
    )
    (net (code "103") (name "Net-(U1-COM7)") (class "Default")
      (node (ref "R1") (pin "1") (pinfunction "1_1") (pintype "passive"))
      (node (ref "U1") (pin "30") (pinfunction "COM7_30") (pintype "passive"))
    )
    (net (code "104") (name "Net-(U1-DATA)") (class "Default")
      (node (ref "U1") (pin "16") (pinfunction "DATA_16") (pintype "passive"))
      (node (ref "U4") (pin "16") (pinfunction "DATA_16") (pintype "passive"))
      (node (ref "U5") (pin "40") (pinfunction "CTS1,AD0,P0.0_40") (pintype "passive"))
    )
    (net (code "105") (name "Net-(U1-~{CS})") (class "Default")
      (node (ref "U1") (pin "19") (pinfunction "~{CS}_19") (pintype "passive"))
      (node (ref "U5") (pin "37") (pinfunction "RTS0,AD3,P0.3_37") (pintype "passive"))
    )
    (net (code "106") (name "Net-(U1-~{RD})") (class "Default")
      (node (ref "U1") (pin "18") (pinfunction "~{RD}_18") (pintype "passive"))
      (node (ref "U4") (pin "18") (pinfunction "~{RD}_18") (pintype "passive"))
      (node (ref "U5") (pin "38") (pinfunction "CTS0,AD2,P0.2_38") (pintype "passive"))
    )
    (net (code "107") (name "Net-(U1-~{WR})") (class "Default")
      (node (ref "U1") (pin "17") (pinfunction "~{WR}_17") (pintype "passive"))
      (node (ref "U4") (pin "17") (pinfunction "~{WR}_17") (pintype "passive"))
      (node (ref "U5") (pin "39") (pinfunction "RTS1,AD1,P0.1_39") (pintype "passive"))
    )
    (net (code "108") (name "Net-(U3-RXD)") (class "Default")
      (node (ref "U3") (pin "25") (pinfunction "RXD_25") (pintype "passive"))
      (node (ref "U5") (pin "7") (pinfunction "TXD,P3.1_7") (pintype "passive"))
    )
    (net (code "109") (name "Net-(U3-TXD)") (class "Default")
      (node (ref "U3") (pin "26") (pinfunction "TXD_26") (pintype "passive"))
      (node (ref "U5") (pin "5") (pinfunction "RXD,P3.0_5") (pintype "passive"))
    )
    (net (code "110") (name "Net-(U3-VDD)") (class "Default")
      (node (ref "C1") (pin "2") (pinfunction "2_2") (pintype "passive"))
      (node (ref "U3") (pin "6") (pinfunction "VDD_6") (pintype "passive"))
    )
    (net (code "111") (name "Net-(U3-{slash}RST)") (class "Default")
      (node (ref "R7") (pin "2") (pinfunction "2_2") (pintype "passive"))
      (node (ref "U3") (pin "9") (pinfunction "/RST_9") (pintype "passive"))
    )
    (net (code "112") (name "Net-(U4-COM0)") (class "Default")
      (node (ref "R8") (pin "4") (pinfunction "4_4") (pintype "passive"))
      (node (ref "U4") (pin "22") (pinfunction "COM0_22") (pintype "passive"))
    )
    (net (code "113") (name "Net-(U4-COM1)") (class "Default")
      (node (ref "R8") (pin "3") (pinfunction "3_3") (pintype "passive"))
      (node (ref "U4") (pin "23") (pinfunction "COM1_23") (pintype "passive"))
    )
    (net (code "114") (name "Net-(U4-COM2)") (class "Default")
      (node (ref "R8") (pin "2") (pinfunction "2_2") (pintype "passive"))
      (node (ref "U4") (pin "24") (pinfunction "COM2_24") (pintype "passive"))
    )
    (net (code "115") (name "Net-(U4-COM3)") (class "Default")
      (node (ref "R8") (pin "1") (pinfunction "1_1") (pintype "passive"))
      (node (ref "U4") (pin "26") (pinfunction "COM3_26") (pintype "passive"))
    )
    (net (code "116") (name "Net-(U4-COM4)") (class "Default")
      (node (ref "R6") (pin "4") (pinfunction "4_4") (pintype "passive"))
      (node (ref "U4") (pin "27") (pinfunction "COM4_27") (pintype "passive"))
    )
    (net (code "117") (name "Net-(U4-COM5)") (class "Default")
      (node (ref "R6") (pin "3") (pinfunction "3_3") (pintype "passive"))
      (node (ref "U4") (pin "28") (pinfunction "COM5_28") (pintype "passive"))
    )
    (net (code "118") (name "Net-(U4-COM6)") (class "Default")
      (node (ref "R6") (pin "2") (pinfunction "2_2") (pintype "passive"))
      (node (ref "U4") (pin "29") (pinfunction "COM6_29") (pintype "passive"))
    )
    (net (code "119") (name "Net-(U4-COM7)") (class "Default")
      (node (ref "R6") (pin "1") (pinfunction "1_1") (pintype "passive"))
      (node (ref "U4") (pin "30") (pinfunction "COM7_30") (pintype "passive"))
    )
    (net (code "120") (name "Net-(U4-~{CS})") (class "Default")
      (node (ref "U4") (pin "19") (pinfunction "~{CS}_19") (pintype "passive"))
      (node (ref "U5") (pin "36") (pinfunction "P4.1,PWM1_36") (pintype "passive"))
    )
    (net (code "121") (name "Net-(U5-P2.0,AD8,PWM0)") (class "Default")
      (node (ref "R16") (pin "4") (pinfunction "4_4") (pintype "passive"))
      (node (ref "S4") (pin "1") (pinfunction "1_1") (pintype "passive"))
      (node (ref "S4") (pin "4") (pinfunction "4_4") (pintype "passive"))
      (node (ref "U5") (pin "19") (pinfunction "P2.0,AD8,PWM0_19") (pintype "passive"))
    )
    (net (code "122") (name "Net-(U5-P2.1,AD9,PWM1)") (class "Default")
      (node (ref "R16") (pin "3") (pinfunction "3_3") (pintype "passive"))
      (node (ref "S3") (pin "1") (pinfunction "1_1") (pintype "passive"))
      (node (ref "S3") (pin "4") (pinfunction "4_4") (pintype "passive"))
      (node (ref "U5") (pin "20") (pinfunction "P2.1,AD9,PWM1_20") (pintype "passive"))
    )
    (net (code "123") (name "Net-(U5-P2.2,AD10,PWM2)") (class "Default")
      (node (ref "R16") (pin "2") (pinfunction "2_2") (pintype "passive"))
      (node (ref "S2") (pin "1") (pinfunction "1_1") (pintype "passive"))
      (node (ref "S2") (pin "4") (pinfunction "4_4") (pintype "passive"))
      (node (ref "U5") (pin "21") (pinfunction "P2.2,AD10,PWM2_21") (pintype "passive"))
    )
    (net (code "124") (name "Net-(U5-P2.3,AD11,PWM3)") (class "Default")
      (node (ref "R16") (pin "1") (pinfunction "1_1") (pintype "passive"))
      (node (ref "S1") (pin "1") (pinfunction "1_1") (pintype "passive"))
      (node (ref "S1") (pin "4") (pinfunction "4_4") (pintype "passive"))
      (node (ref "U5") (pin "22") (pinfunction "P2.3,AD11,PWM3_22") (pintype "passive"))
    )
    (net (code "125") (name "Net-(U5-P4.0,PWM0)") (class "Default")
      (node (ref "R12") (pin "2") (pinfunction "2_2") (pintype "passive"))
      (node (ref "U5") (pin "24") (pinfunction "P4.0,PWM0_24") (pintype "passive"))
    )
    (net (code "126") (name "Net-(U5-SCL,T1,P3.5)") (class "Default")
      (node (ref "R11") (pin "4") (pinfunction "4_4") (pintype "passive"))
      (node (ref "U5") (pin "11") (pinfunction "SCL,T1,P3.5_11") (pintype "passive"))
      (node (ref "U6") (pin "4") (pinfunction "SCL_4") (pintype "passive"))
      (node (ref "U7") (pin "8") (pinfunction "SCL_8") (pintype "passive"))
    )
    (net (code "127") (name "Net-(U5-SDA,T0,P3.4)") (class "Default")
      (node (ref "R11") (pin "3") (pinfunction "3_3") (pintype "passive"))
      (node (ref "U5") (pin "10") (pinfunction "SDA,T0,P3.4_10") (pintype "passive"))
      (node (ref "U6") (pin "2") (pinfunction "SDA_2") (pintype "passive"))
      (node (ref "U7") (pin "7") (pinfunction "SDA_7") (pintype "passive"))
    )
    (net (code "128") (name "Net-(U5-STADC,INT0,P3.2)") (class "Default")
      (node (ref "R11") (pin "1") (pinfunction "1_1") (pintype "passive"))
      (node (ref "U5") (pin "8") (pinfunction "STADC,INT0,P3.2_8") (pintype "passive"))
      (node (ref "U7") (pin "3") (pinfunction "~{INT}/SQW_3") (pintype "passive"))
    )
    (net (code "129") (name "Net-(U5-T2,AIN0,P1.0)") (class "Default")
      (node (ref "R3") (pin "2") (pinfunction "2_2") (pintype "passive"))
      (node (ref "R4") (pin "1") (pinfunction "1_1") (pintype "passive"))
      (node (ref "U5") (pin "43") (pinfunction "T2,AIN0,P1.0_43") (pintype "passive"))
    )
    (net (code "130") (name "Net-(U7-~{RST})") (class "Default")
      (node (ref "R11") (pin "2") (pinfunction "2_2") (pintype "passive"))
      (node (ref "U7") (pin "4") (pinfunction "~{RST}_4") (pintype "passive"))
    )
    (net (code "131") (name "VCC") (class "Default")
      (node (ref "C2") (pin "2") (pinfunction "2_2") (pintype "passive"))
      (node (ref "C4") (pin "1") (pinfunction "1_1") (pintype "passive"))
      (node (ref "C5") (pin "2") (pinfunction "2_2") (pintype "passive"))
      (node (ref "J1") (pin "1") (pinfunction "VCC_1") (pintype "passive"))
      (node (ref "P1") (pin "1") (pinfunction "1_1") (pintype "passive"))
      (node (ref "R11") (pin "5") (pinfunction "5_5") (pintype "passive"))
      (node (ref "R11") (pin "6") (pinfunction "6_6") (pintype "passive"))
      (node (ref "R11") (pin "7") (pinfunction "7_7") (pintype "passive"))
      (node (ref "R11") (pin "8") (pinfunction "8_8") (pintype "passive"))
      (node (ref "R13") (pin "2") (pinfunction "2_2") (pintype "passive"))
      (node (ref "R14") (pin "1") (pinfunction "1_1") (pintype "passive"))
      (node (ref "R16") (pin "5") (pinfunction "5_5") (pintype "passive"))
      (node (ref "R16") (pin "6") (pinfunction "6_6") (pintype "passive"))
      (node (ref "R16") (pin "7") (pinfunction "7_7") (pintype "passive"))
      (node (ref "R16") (pin "8") (pinfunction "8_8") (pintype "passive"))
      (node (ref "R4") (pin "2") (pinfunction "2_2") (pintype "passive"))
      (node (ref "R7") (pin "1") (pinfunction "1_1") (pintype "passive"))
      (node (ref "U1") (pin "21") (pinfunction "VDD_21") (pintype "passive"))
      (node (ref "U1") (pin "38") (pinfunction "VDD_38") (pintype "passive"))
      (node (ref "U1") (pin "7") (pinfunction "VDD_7") (pintype "passive"))
      (node (ref "U3") (pin "7") (pinfunction "REGIN_7") (pintype "passive"))
      (node (ref "U3") (pin "8") (pinfunction "VBUS_8") (pintype "passive"))
      (node (ref "U4") (pin "21") (pinfunction "VDD_21") (pintype "passive"))
      (node (ref "U4") (pin "38") (pinfunction "VDD_38") (pintype "passive"))
      (node (ref "U4") (pin "7") (pinfunction "VDD_7") (pintype "passive"))
      (node (ref "U5") (pin "41") (pinfunction "VDD_41") (pintype "passive"))
      (node (ref "U6") (pin "1") (pinfunction "VCC_1") (pintype "passive"))
      (node (ref "U7") (pin "2") (pinfunction "VCC_2") (pintype "passive"))
      (node (ref "U8") (pin "1") (pinfunction "LEAD+_1") (pintype "passive"))
    )
    (net (code "132") (name "unconnected-(J1-ID-Pad4)") (class "Default")
      (node (ref "J1") (pin "4") (pinfunction "ID_4") (pintype "passive"))
    )
    (net (code "133") (name "unconnected-(U3-CTS-Pad23)") (class "Default")
      (node (ref "U3") (pin "23") (pinfunction "CTS_23") (pintype "passive"))
    )
    (net (code "134") (name "unconnected-(U3-DCD-Pad1)") (class "Default")
      (node (ref "U3") (pin "1") (pinfunction "DCD_1") (pintype "passive"))
    )
    (net (code "135") (name "unconnected-(U3-DSR-Pad27)") (class "Default")
      (node (ref "U3") (pin "27") (pinfunction "DSR_27") (pintype "passive"))
    )
    (net (code "136") (name "unconnected-(U3-DTR-Pad28)") (class "Default")
      (node (ref "U3") (pin "28") (pinfunction "DTR_28") (pintype "passive"))
    )
    (net (code "137") (name "unconnected-(U3-NC-Pad10)") (class "Default")
      (node (ref "U3") (pin "10") (pinfunction "NC_10") (pintype "passive"))
    )
    (net (code "138") (name "unconnected-(U3-NC-Pad13)") (class "Default")
      (node (ref "U3") (pin "13") (pinfunction "NC_13") (pintype "passive"))
    )
    (net (code "139") (name "unconnected-(U3-NC-Pad14)") (class "Default")
      (node (ref "U3") (pin "14") (pinfunction "NC_14") (pintype "passive"))
    )
    (net (code "140") (name "unconnected-(U3-NC-Pad15)") (class "Default")
      (node (ref "U3") (pin "15") (pinfunction "NC_15") (pintype "passive"))
    )
    (net (code "141") (name "unconnected-(U3-NC-Pad16)") (class "Default")
      (node (ref "U3") (pin "16") (pinfunction "NC_16") (pintype "passive"))
    )
    (net (code "142") (name "unconnected-(U3-NC-Pad17)") (class "Default")
      (node (ref "U3") (pin "17") (pinfunction "NC_17") (pintype "passive"))
    )
    (net (code "143") (name "unconnected-(U3-NC-Pad18)") (class "Default")
      (node (ref "U3") (pin "18") (pinfunction "NC_18") (pintype "passive"))
    )
    (net (code "144") (name "unconnected-(U3-NC-Pad19)") (class "Default")
      (node (ref "U3") (pin "19") (pinfunction "NC_19") (pintype "passive"))
    )
    (net (code "145") (name "unconnected-(U3-NC-Pad20)") (class "Default")
      (node (ref "U3") (pin "20") (pinfunction "NC_20") (pintype "passive"))
    )
    (net (code "146") (name "unconnected-(U3-NC-Pad21)") (class "Default")
      (node (ref "U3") (pin "21") (pinfunction "NC_21") (pintype "passive"))
    )
    (net (code "147") (name "unconnected-(U3-NC-Pad22)") (class "Default")
      (node (ref "U3") (pin "22") (pinfunction "NC_22") (pintype "passive"))
    )
    (net (code "148") (name "unconnected-(U3-RI-Pad2)") (class "Default")
      (node (ref "U3") (pin "2") (pinfunction "RI_2") (pintype "passive"))
    )
    (net (code "149") (name "unconnected-(U3-RTS-Pad24)") (class "Default")
      (node (ref "U3") (pin "24") (pinfunction "RTS_24") (pintype "passive"))
    )
    (net (code "150") (name "unconnected-(U5-LDO_CAP-Pad18)") (class "Default")
      (node (ref "U5") (pin "18") (pinfunction "LDO_CAP_18") (pintype "passive"))
    )
    (net (code "151") (name "unconnected-(U5-MCLK,INT1,P3.3-Pad9)") (class "Default")
      (node (ref "U5") (pin "9") (pinfunction "MCLK,INT1,P3.3_9") (pintype "passive"))
    )
    (net (code "152") (name "unconnected-(U5-MISO_0,AIN6,P1.6-Pad2)") (class "Default")
      (node (ref "U5") (pin "2") (pinfunction "MISO_0,AIN6,P1.6_2") (pintype "passive"))
    )
    (net (code "153") (name "unconnected-(U5-MOSI_0,AIN5,P1.5-Pad1)") (class "Default")
      (node (ref "U5") (pin "1") (pinfunction "MOSI_0,AIN5,P1.5_1") (pintype "passive"))
    )
    (net (code "154") (name "unconnected-(U5-P0.4,AD4,SPISS1-Pad35)") (class "Default")
      (node (ref "U5") (pin "35") (pinfunction "P0.4,AD4,SPISS1_35") (pintype "passive"))
    )
    (net (code "155") (name "unconnected-(U5-P0.5,AD5,MOSI_1-Pad34)") (class "Default")
      (node (ref "U5") (pin "34") (pinfunction "P0.5,AD5,MOSI_1_34") (pintype "passive"))
    )
    (net (code "156") (name "unconnected-(U5-P0.6,AD6,MISO_1-Pad33)") (class "Default")
      (node (ref "U5") (pin "33") (pinfunction "P0.6,AD6,MISO_1_33") (pintype "passive"))
    )
    (net (code "157") (name "unconnected-(U5-P0.7,AD7,SPICLK1-Pad32)") (class "Default")
      (node (ref "U5") (pin "32") (pinfunction "P0.7,AD7,SPICLK1_32") (pintype "passive"))
    )
    (net (code "158") (name "unconnected-(U5-P2.4,AD12,PWM4-Pad23)") (class "Default")
      (node (ref "U5") (pin "23") (pinfunction "P2.4,AD12,PWM4_23") (pintype "passive"))
    )
    (net (code "159") (name "unconnected-(U5-P2.5,AD13,PWM5-Pad25)") (class "Default")
      (node (ref "U5") (pin "25") (pinfunction "P2.5,AD13,PWM5_25") (pintype "passive"))
    )
    (net (code "160") (name "unconnected-(U5-P2.6,AD14,PWM6-Pad26)") (class "Default")
      (node (ref "U5") (pin "26") (pinfunction "P2.6,AD14,PWM6_26") (pintype "passive"))
    )
    (net (code "161") (name "unconnected-(U5-P2.7,AD15,PWM7-Pad27)") (class "Default")
      (node (ref "U5") (pin "27") (pinfunction "P2.7,AD15,PWM7_27") (pintype "passive"))
    )
    (net (code "162") (name "unconnected-(U5-P3.6~{,W}R,CKO-Pad13)") (class "Default")
      (node (ref "U5") (pin "13") (pinfunction "P3.6~{,W}R,CKO_13") (pintype "passive"))
    )
    (net (code "163") (name "unconnected-(U5-P3.7~{,R}D-Pad14)") (class "Default")
      (node (ref "U5") (pin "14") (pinfunction "P3.7~{,R}D_14") (pintype "passive"))
    )
    (net (code "164") (name "unconnected-(U5-P4.4~{,C}S-Pad28)") (class "Default")
      (node (ref "U5") (pin "28") (pinfunction "P4.4~{,C}S_28") (pintype "passive"))
    )
    (net (code "165") (name "unconnected-(U5-P4.5,ALE-Pad29)") (class "Default")
      (node (ref "U5") (pin "29") (pinfunction "P4.5,ALE_29") (pintype "passive"))
    )
    (net (code "166") (name "unconnected-(U5-PWM2,P4.2-Pad48)") (class "Default")
      (node (ref "U5") (pin "48") (pinfunction "PWM2,P4.2_48") (pintype "passive"))
    )
    (net (code "167") (name "unconnected-(U5-PWM3,P4.3-Pad12)") (class "Default")
      (node (ref "U5") (pin "12") (pinfunction "PWM3,P4.3_12") (pintype "passive"))
    )
    (net (code "168") (name "unconnected-(U5-RXD1,AIN2,P1.2-Pad45)") (class "Default")
      (node (ref "U5") (pin "45") (pinfunction "RXD1,AIN2,P1.2_45") (pintype "passive"))
    )
    (net (code "169") (name "unconnected-(U5-SPICLK0,AIN7,P1.7-Pad3)") (class "Default")
      (node (ref "U5") (pin "3") (pinfunction "SPICLK0,AIN7,P1.7_3") (pintype "passive"))
    )
    (net (code "170") (name "unconnected-(U5-SPISS0,AIN4,P1.4-Pad47)") (class "Default")
      (node (ref "U5") (pin "47") (pinfunction "SPISS0,AIN4,P1.4_47") (pintype "passive"))
    )
    (net (code "171") (name "unconnected-(U5-T3,AIN1,P1.1-Pad44)") (class "Default")
      (node (ref "U5") (pin "44") (pinfunction "T3,AIN1,P1.1_44") (pintype "passive"))
    )
    (net (code "172") (name "unconnected-(U5-TXD1,AIN3,P1.3-Pad46)") (class "Default")
      (node (ref "U5") (pin "46") (pinfunction "TXD1,AIN3,P1.3_46") (pintype "passive"))
    )
    (net (code "173") (name "unconnected-(U5-XTAL1-Pad15)") (class "Default")
      (node (ref "U5") (pin "15") (pinfunction "XTAL1_15") (pintype "passive"))
    )
    (net (code "174") (name "unconnected-(U5-XTAL2-Pad16)") (class "Default")
      (node (ref "U5") (pin "16") (pinfunction "XTAL2_16") (pintype "passive"))
    )
    (net (code "175") (name "unconnected-(U7-32KHZ-Pad1)") (class "Default")
      (node (ref "U7") (pin "1") (pinfunction "32KHZ_1") (pintype "passive"))
    )
  )
)
